# design.net
KiCad netlist of a schematic drawn in EasyEDA Pro
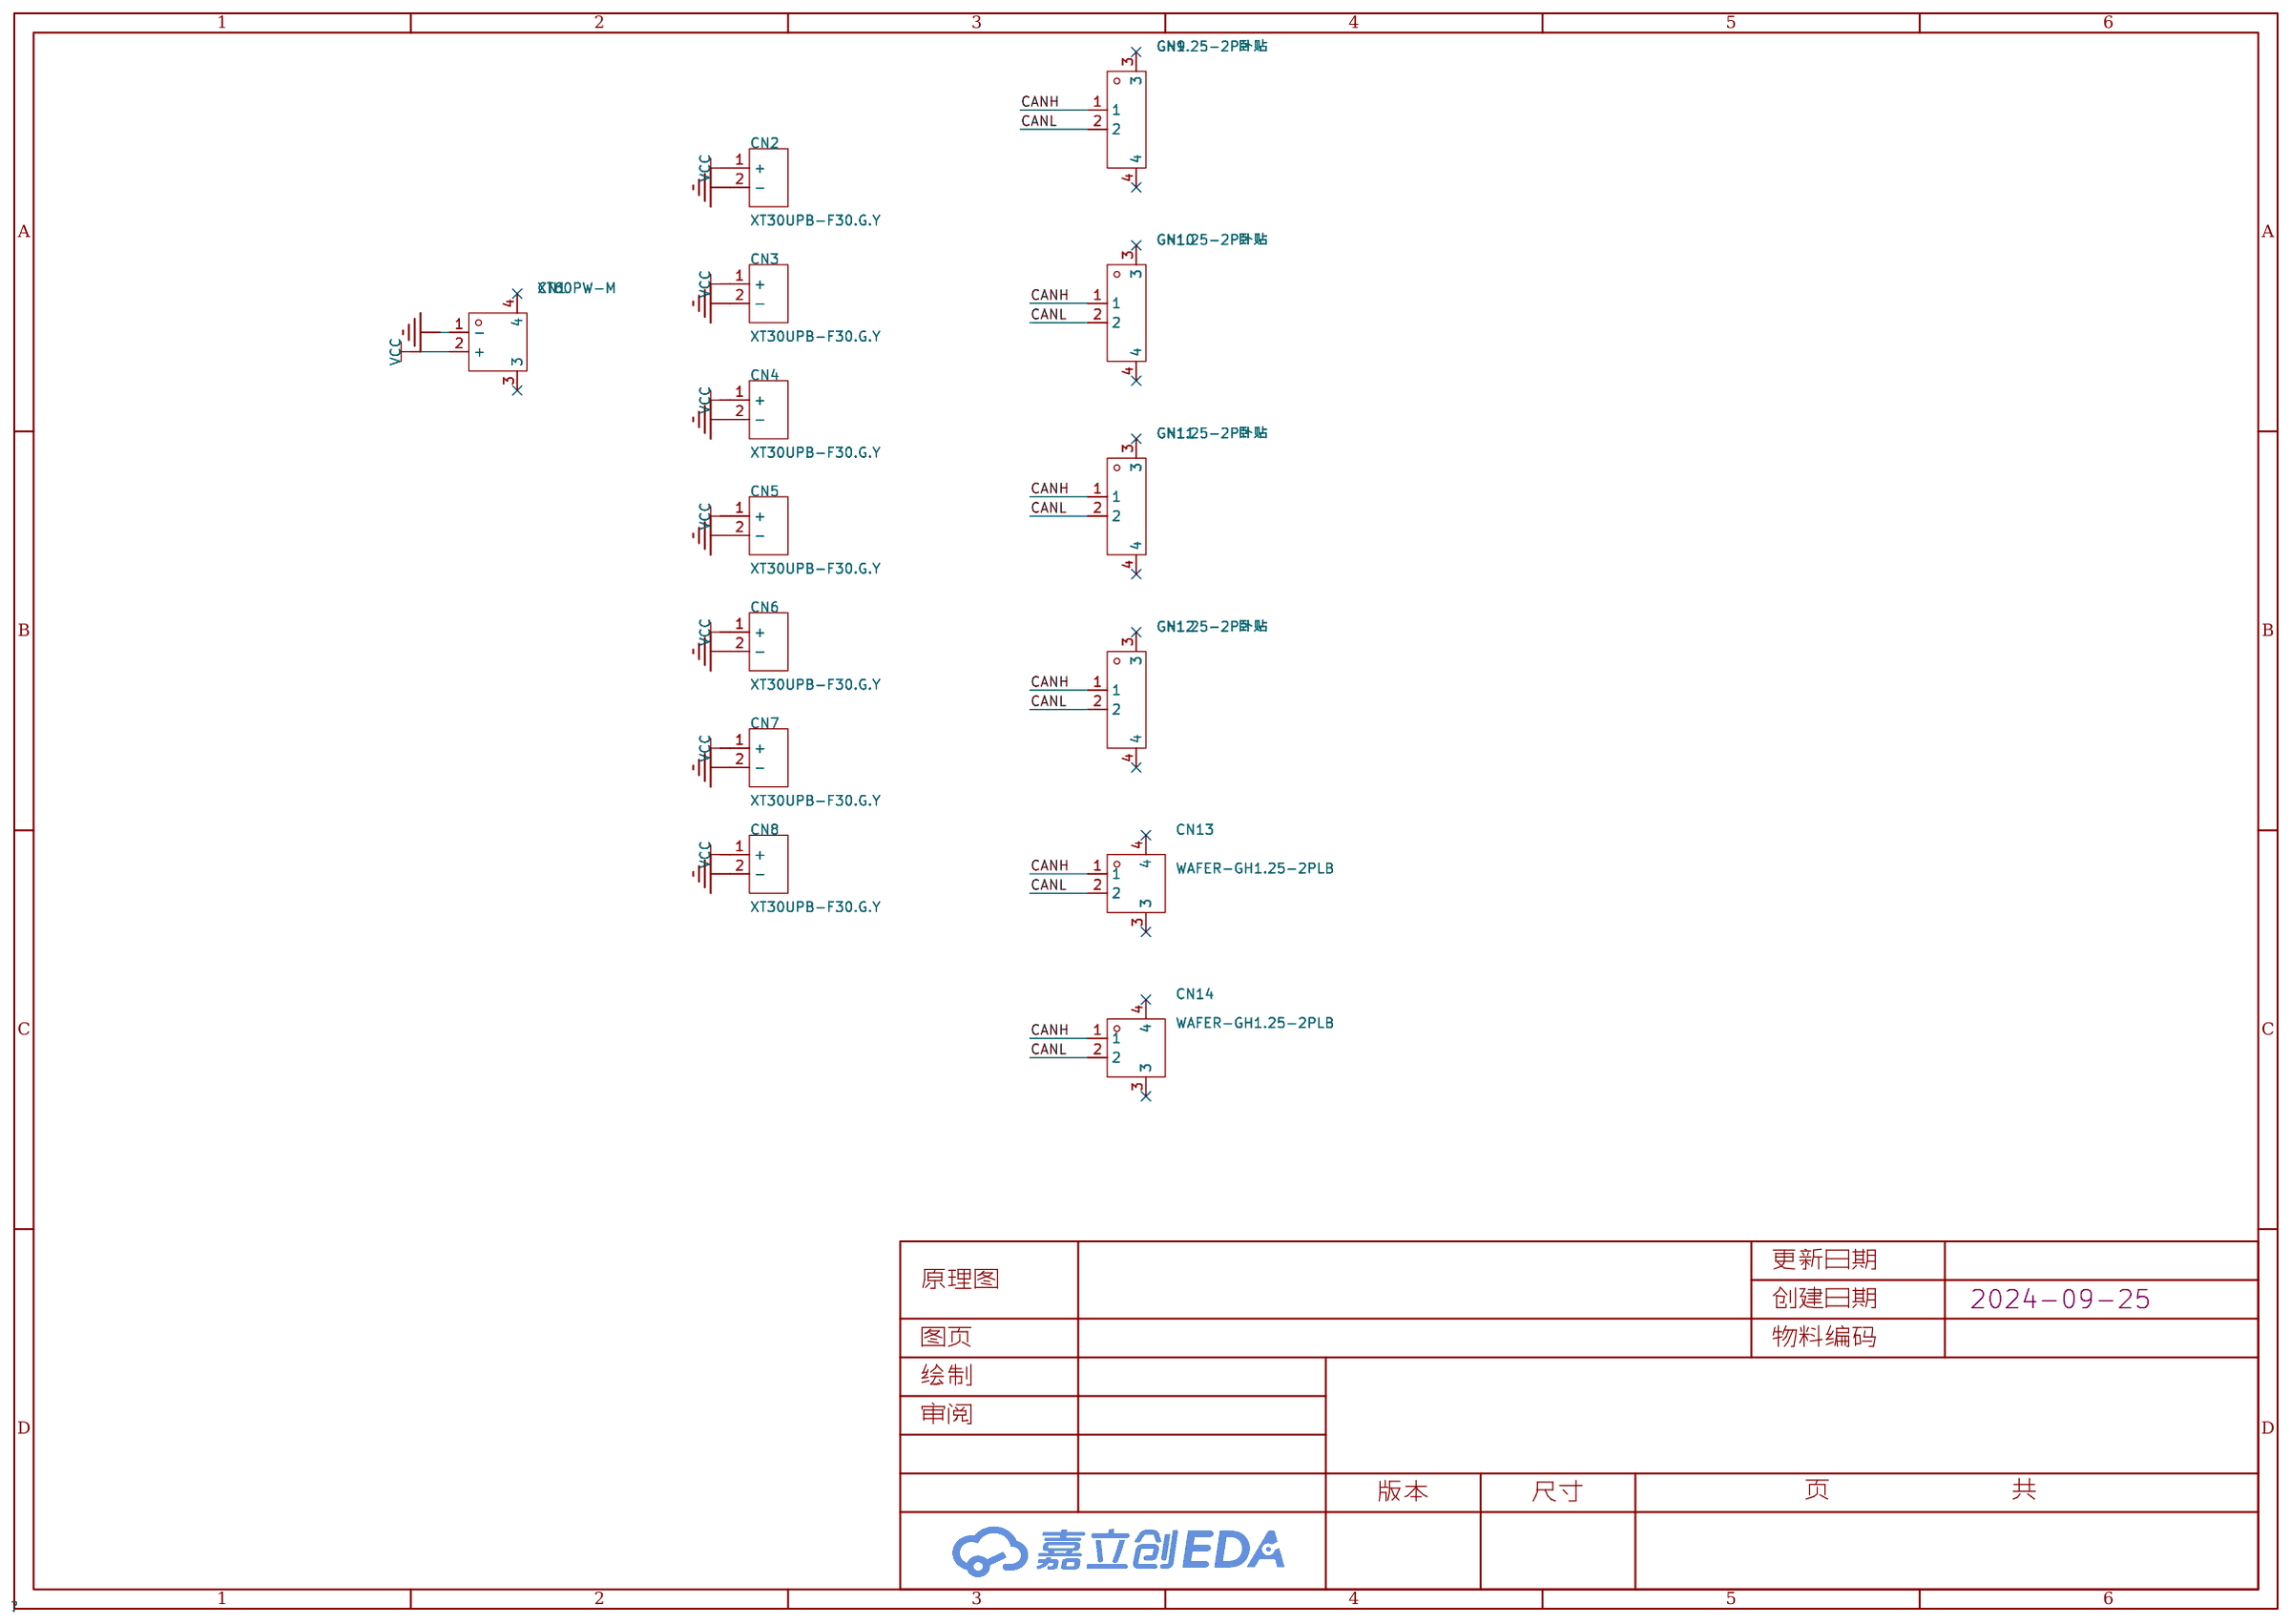
[diagram p0: schematic sheet]

(export (version "E")
  (design (tool "Eeschema 10.0.6"))
  (components
    (comp (ref "CN1")
      (value "XT60PW-M")
      (footprint "easyedapro:CONN-TH_XT60PW-M")
      (description "类别:-;类型1:-;")
      (fields (field (name "Manufacturer") "AMASS(艾迈斯)"))
      (libsource (lib "easyedapro") (part "XT60PW-M"))
    )
    (comp (ref "CN2")
      (value "XT30UPB-F30.G.Y")
      (footprint "easyedapro:CONN-TH_XT30UPB-F")
      (description "类别:-;类型1:-;")
      (fields (field (name "Manufacturer") "AMASS(艾迈斯)"))
      (libsource (lib "easyedapro") (part "XT30UPB-F"))
    )
    (comp (ref "CN3")
      (value "XT30UPB-F30.G.Y")
      (footprint "easyedapro:CONN-TH_XT30UPB-F")
      (description "类别:-;类型1:-;")
      (fields (field (name "Manufacturer") "AMASS(艾迈斯)"))
      (libsource (lib "easyedapro") (part "XT30UPB-F"))
    )
    (comp (ref "CN4")
      (value "XT30UPB-F30.G.Y")
      (footprint "easyedapro:CONN-TH_XT30UPB-F")
      (description "类别:-;类型1:-;")
      (fields (field (name "Manufacturer") "AMASS(艾迈斯)"))
      (libsource (lib "easyedapro") (part "XT30UPB-F"))
    )
    (comp (ref "CN5")
      (value "XT30UPB-F30.G.Y")
      (footprint "easyedapro:CONN-TH_XT30UPB-F")
      (description "类别:-;类型1:-;")
      (fields (field (name "Manufacturer") "AMASS(艾迈斯)"))
      (libsource (lib "easyedapro") (part "XT30UPB-F"))
    )
    (comp (ref "CN6")
      (value "XT30UPB-F30.G.Y")
      (footprint "easyedapro:CONN-TH_XT30UPB-F")
      (description "类别:-;类型1:-;")
      (fields (field (name "Manufacturer") "AMASS(艾迈斯)"))
      (libsource (lib "easyedapro") (part "XT30UPB-F"))
    )
    (comp (ref "CN7")
      (value "XT30UPB-F30.G.Y")
      (footprint "easyedapro:CONN-TH_XT30UPB-F")
      (description "类别:-;类型1:-;")
      (fields (field (name "Manufacturer") "AMASS(艾迈斯)"))
      (libsource (lib "easyedapro") (part "XT30UPB-F"))
    )
    (comp (ref "CN8")
      (value "XT30UPB-F30.G.Y")
      (footprint "easyedapro:CONN-TH_XT30UPB-F")
      (description "类别:-;类型1:-;")
      (fields (field (name "Manufacturer") "AMASS(艾迈斯)"))
      (libsource (lib "easyedapro") (part "XT30UPB-F"))
    )
    (comp (ref "CN9")
      (value "GH1.25-2P卧贴")
      (footprint "easyedapro:CONN-SMD_2P-P1.25_X1251WRS-02HF-LPSW")
      (libsource (lib "easyedapro") (part "GH1.25-2P卧贴_C9900015099"))
    )
    (comp (ref "CN10")
      (value "GH1.25-2P卧贴")
      (footprint "easyedapro:CONN-SMD_2P-P1.25_X1251WRS-02HF-LPSW")
      (libsource (lib "easyedapro") (part "GH1.25-2P卧贴_C9900015099"))
    )
    (comp (ref "CN11")
      (value "GH1.25-2P卧贴")
      (footprint "easyedapro:CONN-SMD_2P-P1.25_X1251WRS-02HF-LPSW")
      (libsource (lib "easyedapro") (part "GH1.25-2P卧贴_C9900015099"))
    )
    (comp (ref "CN12")
      (value "GH1.25-2P卧贴")
      (footprint "easyedapro:CONN-SMD_2P-P1.25_X1251WRS-02HF-LPSW")
      (libsource (lib "easyedapro") (part "GH1.25-2P卧贴_C9900015099"))
    )
    (comp (ref "CN13")
      (value "WAFER-GH1.25-2PLB")
      (footprint "easyedapro:CONN-TH_2P-P1.25_XUNPU_WAFER-GH1.25-2PLB")
      (description "插针结构:1x2P;间距:1.25mm;安装方式:立贴;参考系列:GH;总PIN数:2P;排数:1;每排PIN数:2;额定电流:1A;工作温度范围:-25°C~+85°C;")
      (fields (field (name "Manufacturer") "XUNPU(讯普)"))
      (libsource (lib "easyedapro") (part "WAFER-GH1.25-2PLB"))
    )
    (comp (ref "CN14")
      (value "WAFER-GH1.25-2PLB")
      (footprint "easyedapro:CONN-TH_2P-P1.25_XUNPU_WAFER-GH1.25-2PLB")
      (description "插针结构:1x2P;间距:1.25mm;安装方式:立贴;参考系列:GH;总PIN数:2P;排数:1;每排PIN数:2;额定电流:1A;工作温度范围:-25°C~+85°C;")
      (fields (field (name "Manufacturer") "XUNPU(讯普)"))
      (libsource (lib "easyedapro") (part "WAFER-GH1.25-2PLB"))
    )
  )
  (nets
    (net (code "1") (name "/CANH") (class "Default")
      (node (ref "CN10") (pin "1") (pinfunction "1_1") (pintype "unspecified"))
      (node (ref "CN11") (pin "1") (pinfunction "1_1") (pintype "unspecified"))
      (node (ref "CN12") (pin "1") (pinfunction "1_1") (pintype "unspecified"))
      (node (ref "CN13") (pin "1") (pinfunction "1_1") (pintype "unspecified"))
      (node (ref "CN14") (pin "1") (pinfunction "1_1") (pintype "unspecified"))
      (node (ref "CN9") (pin "1") (pinfunction "1_1") (pintype "unspecified"))
    )
    (net (code "2") (name "/CANL") (class "Default")
      (node (ref "CN10") (pin "2") (pinfunction "2_2") (pintype "unspecified"))
      (node (ref "CN11") (pin "2") (pinfunction "2_2") (pintype "unspecified"))
      (node (ref "CN12") (pin "2") (pinfunction "2_2") (pintype "unspecified"))
      (node (ref "CN13") (pin "2") (pinfunction "2_2") (pintype "unspecified"))
      (node (ref "CN14") (pin "2") (pinfunction "2_2") (pintype "unspecified"))
      (node (ref "CN9") (pin "2") (pinfunction "2_2") (pintype "unspecified"))
    )
    (net (code "3") (name "GND") (class "Default")
      (node (ref "CN1") (pin "1") (pinfunction "-_1") (pintype "unspecified"))
      (node (ref "CN2") (pin "2") (pinfunction "-_2") (pintype "unspecified"))
      (node (ref "CN3") (pin "2") (pinfunction "-_2") (pintype "unspecified"))
      (node (ref "CN4") (pin "2") (pinfunction "-_2") (pintype "unspecified"))
      (node (ref "CN5") (pin "2") (pinfunction "-_2") (pintype "unspecified"))
      (node (ref "CN6") (pin "2") (pinfunction "-_2") (pintype "unspecified"))
      (node (ref "CN7") (pin "2") (pinfunction "-_2") (pintype "unspecified"))
      (node (ref "CN8") (pin "2") (pinfunction "-_2") (pintype "unspecified"))
    )
    (net (code "4") (name "VCC") (class "Default")
      (node (ref "CN1") (pin "2") (pinfunction "+_2") (pintype "unspecified"))
      (node (ref "CN2") (pin "1") (pinfunction "+_1") (pintype "unspecified"))
      (node (ref "CN3") (pin "1") (pinfunction "+_1") (pintype "unspecified"))
      (node (ref "CN4") (pin "1") (pinfunction "+_1") (pintype "unspecified"))
      (node (ref "CN5") (pin "1") (pinfunction "+_1") (pintype "unspecified"))
      (node (ref "CN6") (pin "1") (pinfunction "+_1") (pintype "unspecified"))
      (node (ref "CN7") (pin "1") (pinfunction "+_1") (pintype "unspecified"))
      (node (ref "CN8") (pin "1") (pinfunction "+_1") (pintype "unspecified"))
    )
    (net (code "5") (name "unconnected-(CN1-Pad3)") (class "Default")
      (node (ref "CN1") (pin "3") (pinfunction "3_3") (pintype "unspecified+no_connect"))
    )
    (net (code "6") (name "unconnected-(CN1-Pad4)") (class "Default")
      (node (ref "CN1") (pin "4") (pinfunction "4_4") (pintype "unspecified+no_connect"))
    )
    (net (code "7") (name "unconnected-(CN9-Pad3)") (class "Default")
      (node (ref "CN9") (pin "3") (pinfunction "3_3") (pintype "unspecified+no_connect"))
    )
    (net (code "8") (name "unconnected-(CN9-Pad4)") (class "Default")
      (node (ref "CN9") (pin "4") (pinfunction "4_4") (pintype "unspecified+no_connect"))
    )
    (net (code "9") (name "unconnected-(CN10-Pad3)") (class "Default")
      (node (ref "CN10") (pin "3") (pinfunction "3_3") (pintype "unspecified+no_connect"))
    )
    (net (code "10") (name "unconnected-(CN10-Pad4)") (class "Default")
      (node (ref "CN10") (pin "4") (pinfunction "4_4") (pintype "unspecified+no_connect"))
    )
    (net (code "11") (name "unconnected-(CN11-Pad3)") (class "Default")
      (node (ref "CN11") (pin "3") (pinfunction "3_3") (pintype "unspecified+no_connect"))
    )
    (net (code "12") (name "unconnected-(CN11-Pad4)") (class "Default")
      (node (ref "CN11") (pin "4") (pinfunction "4_4") (pintype "unspecified+no_connect"))
    )
    (net (code "13") (name "unconnected-(CN12-Pad3)") (class "Default")
      (node (ref "CN12") (pin "3") (pinfunction "3_3") (pintype "unspecified+no_connect"))
    )
    (net (code "14") (name "unconnected-(CN12-Pad4)") (class "Default")
      (node (ref "CN12") (pin "4") (pinfunction "4_4") (pintype "unspecified+no_connect"))
    )
    (net (code "15") (name "unconnected-(CN13-Pad3)") (class "Default")
      (node (ref "CN13") (pin "3") (pinfunction "3_3") (pintype "unspecified+no_connect"))
    )
    (net (code "16") (name "unconnected-(CN13-Pad4)") (class "Default")
      (node (ref "CN13") (pin "4") (pinfunction "4_4") (pintype "unspecified+no_connect"))
    )
    (net (code "17") (name "unconnected-(CN14-Pad3)") (class "Default")
      (node (ref "CN14") (pin "3") (pinfunction "3_3") (pintype "unspecified+no_connect"))
    )
    (net (code "18") (name "unconnected-(CN14-Pad4)") (class "Default")
      (node (ref "CN14") (pin "4") (pinfunction "4_4") (pintype "unspecified+no_connect"))
    )
  )
)
